# 1-Schematic_plaidcomp_prototype.net
KiCad netlist of a schematic drawn in EasyEDA
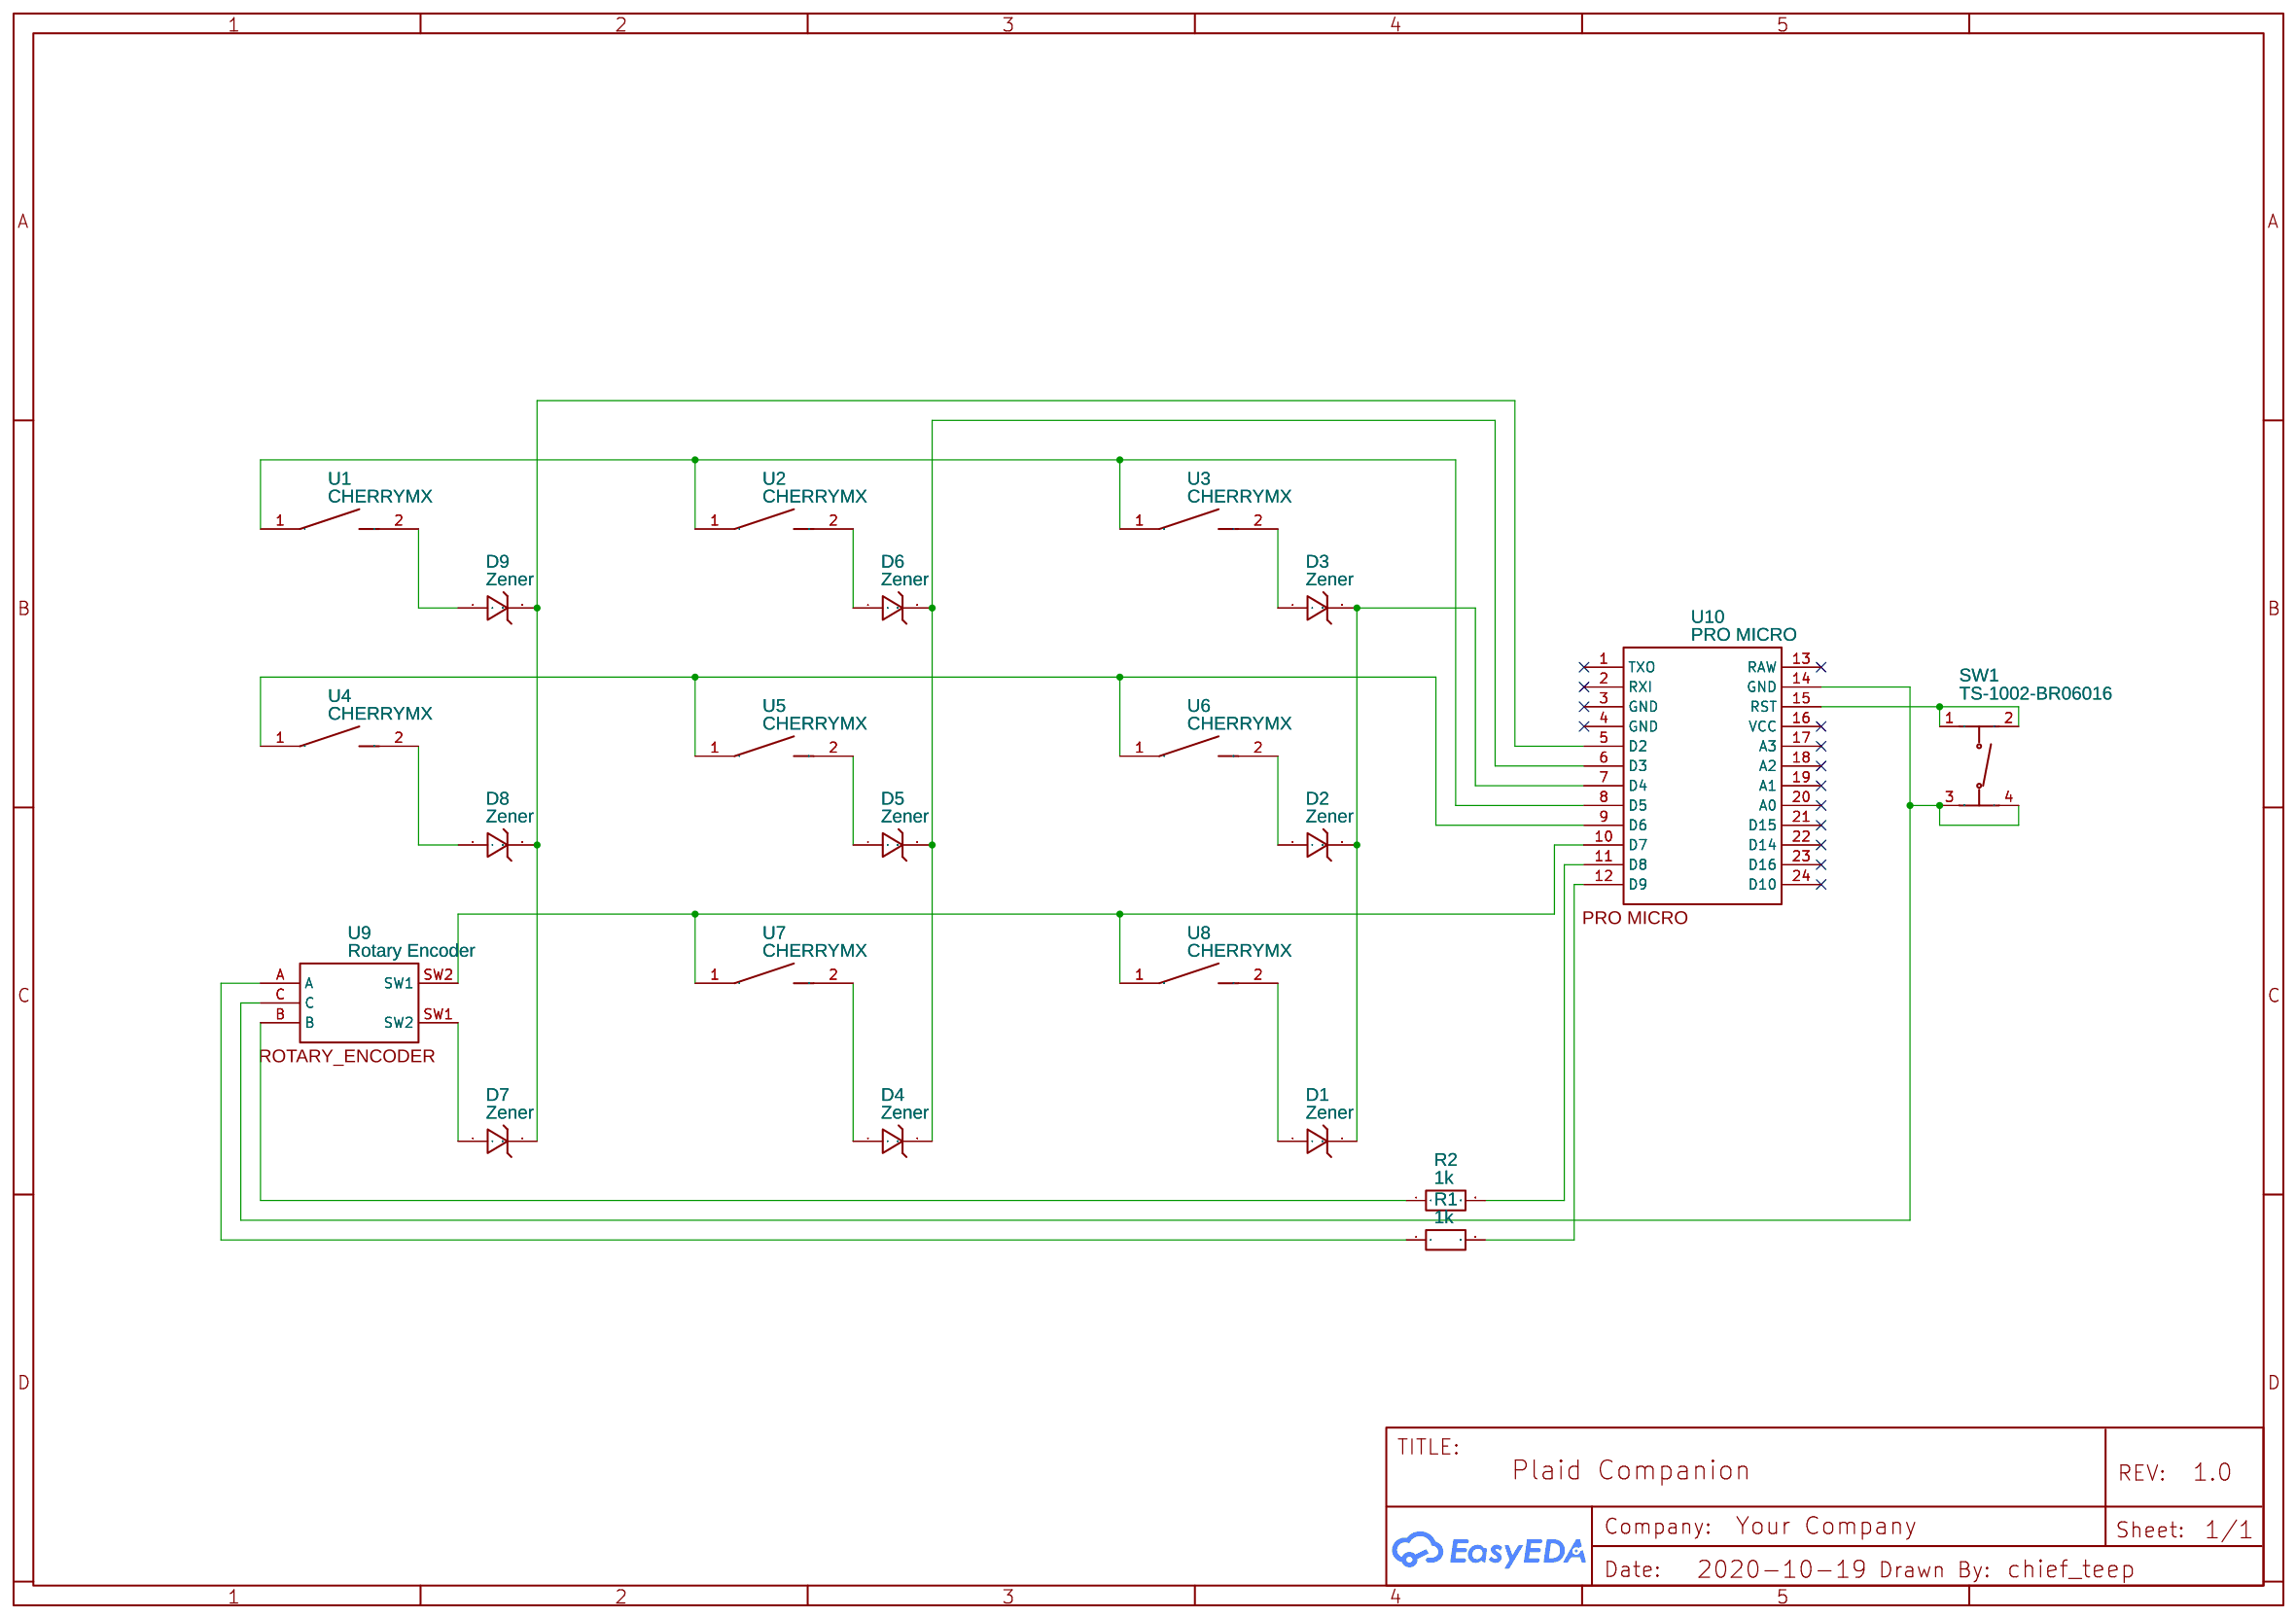
[diagram p0: schematic sheet]

(export (version "E")
  (design (tool "Eeschema 10.0.6"))
  (components
    (comp (ref "D1") (value "Zener") (libsource (lib "") (part "Zener")))
    (comp (ref "D2") (value "Zener") (libsource (lib "") (part "Zener")))
    (comp (ref "D3") (value "Zener") (libsource (lib "") (part "Zener")))
    (comp (ref "D4") (value "Zener") (libsource (lib "") (part "Zener")))
    (comp (ref "D5") (value "Zener") (libsource (lib "") (part "Zener")))
    (comp (ref "D6") (value "Zener") (libsource (lib "") (part "Zener")))
    (comp (ref "D7") (value "Zener") (libsource (lib "") (part "Zener")))
    (comp (ref "D8") (value "Zener") (libsource (lib "") (part "Zener")))
    (comp (ref "D9") (value "Zener") (libsource (lib "") (part "Zener")))
    (comp (ref "R1") (value "1k") (libsource (lib "") (part "R_AXIAL-0.3_EU")))
    (comp (ref "R2") (value "1k") (libsource (lib "") (part "R_AXIAL-0.3_EU")))
    (comp (ref "SW1")
      (value "TS-1002-BR06016")
      (fields (field (name "BOM_Supplier Part") "C720295"))
      (libsource (lib "") (part "TS-1002-BR06016"))
    )
    (comp (ref "U1")
      (value "CHERRYMX")
      (fields (field (name "BOM_Manufacturer Part") "CHERRY"))
      (libsource (lib "") (part "CHERRYMX"))
    )
    (comp (ref "U2")
      (value "CHERRYMX")
      (fields (field (name "BOM_Manufacturer Part") "CHERRY"))
      (libsource (lib "") (part "CHERRYMX"))
    )
    (comp (ref "U3")
      (value "CHERRYMX")
      (fields (field (name "BOM_Manufacturer Part") "CHERRY"))
      (libsource (lib "") (part "CHERRYMX"))
    )
    (comp (ref "U4")
      (value "CHERRYMX")
      (fields (field (name "BOM_Manufacturer Part") "CHERRY"))
      (libsource (lib "") (part "CHERRYMX"))
    )
    (comp (ref "U5")
      (value "CHERRYMX")
      (fields (field (name "BOM_Manufacturer Part") "CHERRY"))
      (libsource (lib "") (part "CHERRYMX"))
    )
    (comp (ref "U6")
      (value "CHERRYMX")
      (fields (field (name "BOM_Manufacturer Part") "CHERRY"))
      (libsource (lib "") (part "CHERRYMX"))
    )
    (comp (ref "U7")
      (value "CHERRYMX")
      (fields (field (name "BOM_Manufacturer Part") "CHERRY"))
      (libsource (lib "") (part "CHERRYMX"))
    )
    (comp (ref "U8")
      (value "CHERRYMX")
      (fields (field (name "BOM_Manufacturer Part") "CHERRY"))
      (libsource (lib "") (part "CHERRYMX"))
    )
    (comp (ref "U9") (value "Rotary Encoder") (libsource (lib "") (part "Rotary Encoder")))
    (comp (ref "U10") (value "PRO MICRO") (libsource (lib "") (part "PRO MICRO")))
  )
  (nets
    (net (code "1") (name "Net-(D1-Pad1)") (class "Default")
      (node (ref "D1") (pin "1") (pinfunction "1_1") (pintype "unspecified"))
      (node (ref "U8") (pin "2") (pinfunction "2_2") (pintype "unspecified"))
    )
    (net (code "2") (name "Net-(D2-Pad1)") (class "Default")
      (node (ref "D2") (pin "1") (pinfunction "1_1") (pintype "unspecified"))
      (node (ref "U6") (pin "2") (pinfunction "2_2") (pintype "unspecified"))
    )
    (net (code "3") (name "Net-(D3-Pad1)") (class "Default")
      (node (ref "D3") (pin "1") (pinfunction "1_1") (pintype "unspecified"))
      (node (ref "U3") (pin "2") (pinfunction "2_2") (pintype "unspecified"))
    )
    (net (code "4") (name "Net-(D4-Pad1)") (class "Default")
      (node (ref "D4") (pin "1") (pinfunction "1_1") (pintype "unspecified"))
      (node (ref "U7") (pin "2") (pinfunction "2_2") (pintype "unspecified"))
    )
    (net (code "5") (name "Net-(D5-Pad1)") (class "Default")
      (node (ref "D5") (pin "1") (pinfunction "1_1") (pintype "unspecified"))
      (node (ref "U5") (pin "2") (pinfunction "2_2") (pintype "unspecified"))
    )
    (net (code "6") (name "Net-(D6-Pad1)") (class "Default")
      (node (ref "D6") (pin "1") (pinfunction "1_1") (pintype "unspecified"))
      (node (ref "U2") (pin "2") (pinfunction "2_2") (pintype "unspecified"))
    )
    (net (code "7") (name "Net-(D8-Pad1)") (class "Default")
      (node (ref "D8") (pin "1") (pinfunction "1_1") (pintype "unspecified"))
      (node (ref "U4") (pin "2") (pinfunction "2_2") (pintype "unspecified"))
    )
    (net (code "8") (name "Net-(D9-Pad1)") (class "Default")
      (node (ref "D9") (pin "1") (pinfunction "1_1") (pintype "unspecified"))
      (node (ref "U1") (pin "2") (pinfunction "2_2") (pintype "unspecified"))
    )
    (net (code "9") (name "Net-(R1-Pad1)") (class "Default")
      (node (ref "R1") (pin "1") (pinfunction "1_1") (pintype "unspecified"))
      (node (ref "U9") (pin "A") (pinfunction "A_A") (pintype "unspecified"))
    )
    (net (code "10") (name "Net-(R2-Pad1)") (class "Default")
      (node (ref "R2") (pin "1") (pinfunction "1_1") (pintype "unspecified"))
      (node (ref "U9") (pin "B") (pinfunction "B_B") (pintype "unspecified"))
    )
    (net (code "11") (name "Net-(SW1-Pad3)") (class "Default")
      (node (ref "SW1") (pin "3") (pinfunction "3_3") (pintype "unspecified"))
      (node (ref "SW1") (pin "4") (pinfunction "4_4") (pintype "unspecified"))
      (node (ref "U10") (pin "14") (pinfunction "GND_14") (pintype "unspecified"))
      (node (ref "U9") (pin "C") (pinfunction "C_C") (pintype "unspecified"))
    )
    (net (code "12") (name "Net-(U9-SW2)") (class "Default")
      (node (ref "D7") (pin "1") (pinfunction "1_1") (pintype "unspecified"))
      (node (ref "U9") (pin "SW1") (pinfunction "SW2_SW1") (pintype "unspecified"))
    )
    (net (code "13") (name "Net-(U10-D2)") (class "Default")
      (node (ref "D7") (pin "2") (pinfunction "2_2") (pintype "unspecified"))
      (node (ref "D8") (pin "2") (pinfunction "2_2") (pintype "unspecified"))
      (node (ref "D9") (pin "2") (pinfunction "2_2") (pintype "unspecified"))
      (node (ref "U10") (pin "5") (pinfunction "D2_5") (pintype "unspecified"))
    )
    (net (code "14") (name "Net-(U10-D3)") (class "Default")
      (node (ref "D4") (pin "2") (pinfunction "2_2") (pintype "unspecified"))
      (node (ref "D5") (pin "2") (pinfunction "2_2") (pintype "unspecified"))
      (node (ref "D6") (pin "2") (pinfunction "2_2") (pintype "unspecified"))
      (node (ref "U10") (pin "6") (pinfunction "D3_6") (pintype "unspecified"))
    )
    (net (code "15") (name "Net-(U10-D4)") (class "Default")
      (node (ref "D1") (pin "2") (pinfunction "2_2") (pintype "unspecified"))
      (node (ref "D2") (pin "2") (pinfunction "2_2") (pintype "unspecified"))
      (node (ref "D3") (pin "2") (pinfunction "2_2") (pintype "unspecified"))
      (node (ref "U10") (pin "7") (pinfunction "D4_7") (pintype "unspecified"))
    )
    (net (code "16") (name "Net-(U10-D5)") (class "Default")
      (node (ref "U1") (pin "1") (pinfunction "1_1") (pintype "unspecified"))
      (node (ref "U10") (pin "8") (pinfunction "D5_8") (pintype "unspecified"))
      (node (ref "U2") (pin "1") (pinfunction "1_1") (pintype "unspecified"))
      (node (ref "U3") (pin "1") (pinfunction "1_1") (pintype "unspecified"))
    )
    (net (code "17") (name "Net-(U10-D6)") (class "Default")
      (node (ref "U10") (pin "9") (pinfunction "D6_9") (pintype "unspecified"))
      (node (ref "U4") (pin "1") (pinfunction "1_1") (pintype "unspecified"))
      (node (ref "U5") (pin "1") (pinfunction "1_1") (pintype "unspecified"))
      (node (ref "U6") (pin "1") (pinfunction "1_1") (pintype "unspecified"))
    )
    (net (code "18") (name "Net-(U10-D7)") (class "Default")
      (node (ref "U10") (pin "10") (pinfunction "D7_10") (pintype "unspecified"))
      (node (ref "U7") (pin "1") (pinfunction "1_1") (pintype "unspecified"))
      (node (ref "U8") (pin "1") (pinfunction "1_1") (pintype "unspecified"))
      (node (ref "U9") (pin "SW2") (pinfunction "SW1_SW2") (pintype "unspecified"))
    )
    (net (code "19") (name "Net-(U10-D8)") (class "Default")
      (node (ref "R2") (pin "2") (pinfunction "2_2") (pintype "unspecified"))
      (node (ref "U10") (pin "11") (pinfunction "D8_11") (pintype "unspecified"))
    )
    (net (code "20") (name "Net-(U10-D9)") (class "Default")
      (node (ref "R1") (pin "2") (pinfunction "2_2") (pintype "unspecified"))
      (node (ref "U10") (pin "12") (pinfunction "D9_12") (pintype "unspecified"))
    )
    (net (code "21") (name "Net-(U10-RST)") (class "Default")
      (node (ref "SW1") (pin "1") (pinfunction "1_1") (pintype "unspecified"))
      (node (ref "SW1") (pin "2") (pinfunction "2_2") (pintype "unspecified"))
      (node (ref "U10") (pin "15") (pinfunction "RST_15") (pintype "unspecified"))
    )
    (net (code "22") (name "unconnected-(U10-A0-Pad20)") (class "Default")
      (node (ref "U10") (pin "20") (pinfunction "A0_20") (pintype "unspecified+no_connect"))
    )
    (net (code "23") (name "unconnected-(U10-A1-Pad19)") (class "Default")
      (node (ref "U10") (pin "19") (pinfunction "A1_19") (pintype "unspecified+no_connect"))
    )
    (net (code "24") (name "unconnected-(U10-A2-Pad18)") (class "Default")
      (node (ref "U10") (pin "18") (pinfunction "A2_18") (pintype "unspecified+no_connect"))
    )
    (net (code "25") (name "unconnected-(U10-A3-Pad17)") (class "Default")
      (node (ref "U10") (pin "17") (pinfunction "A3_17") (pintype "unspecified+no_connect"))
    )
    (net (code "26") (name "unconnected-(U10-D10-Pad24)") (class "Default")
      (node (ref "U10") (pin "24") (pinfunction "D10_24") (pintype "unspecified+no_connect"))
    )
    (net (code "27") (name "unconnected-(U10-D14-Pad22)") (class "Default")
      (node (ref "U10") (pin "22") (pinfunction "D14_22") (pintype "unspecified+no_connect"))
    )
    (net (code "28") (name "unconnected-(U10-D15-Pad21)") (class "Default")
      (node (ref "U10") (pin "21") (pinfunction "D15_21") (pintype "unspecified+no_connect"))
    )
    (net (code "29") (name "unconnected-(U10-D16-Pad23)") (class "Default")
      (node (ref "U10") (pin "23") (pinfunction "D16_23") (pintype "unspecified+no_connect"))
    )
    (net (code "30") (name "unconnected-(U10-GND-Pad3)") (class "Default")
      (node (ref "U10") (pin "3") (pinfunction "GND_3") (pintype "unspecified+no_connect"))
    )
    (net (code "31") (name "unconnected-(U10-GND-Pad4)") (class "Default")
      (node (ref "U10") (pin "4") (pinfunction "GND_4") (pintype "unspecified+no_connect"))
    )
    (net (code "32") (name "unconnected-(U10-RAW-Pad13)") (class "Default")
      (node (ref "U10") (pin "13") (pinfunction "RAW_13") (pintype "unspecified+no_connect"))
    )
    (net (code "33") (name "unconnected-(U10-RXI-Pad2)") (class "Default")
      (node (ref "U10") (pin "2") (pinfunction "RXI_2") (pintype "unspecified+no_connect"))
    )
    (net (code "34") (name "unconnected-(U10-TXO-Pad1)") (class "Default")
      (node (ref "U10") (pin "1") (pinfunction "TXO_1") (pintype "unspecified+no_connect"))
    )
    (net (code "35") (name "unconnected-(U10-VCC-Pad16)") (class "Default")
      (node (ref "U10") (pin "16") (pinfunction "VCC_16") (pintype "unspecified+no_connect"))
    )
  )
)
